# X9-Backplane.net
KiCad netlist of a schematic drawn in EAGLE
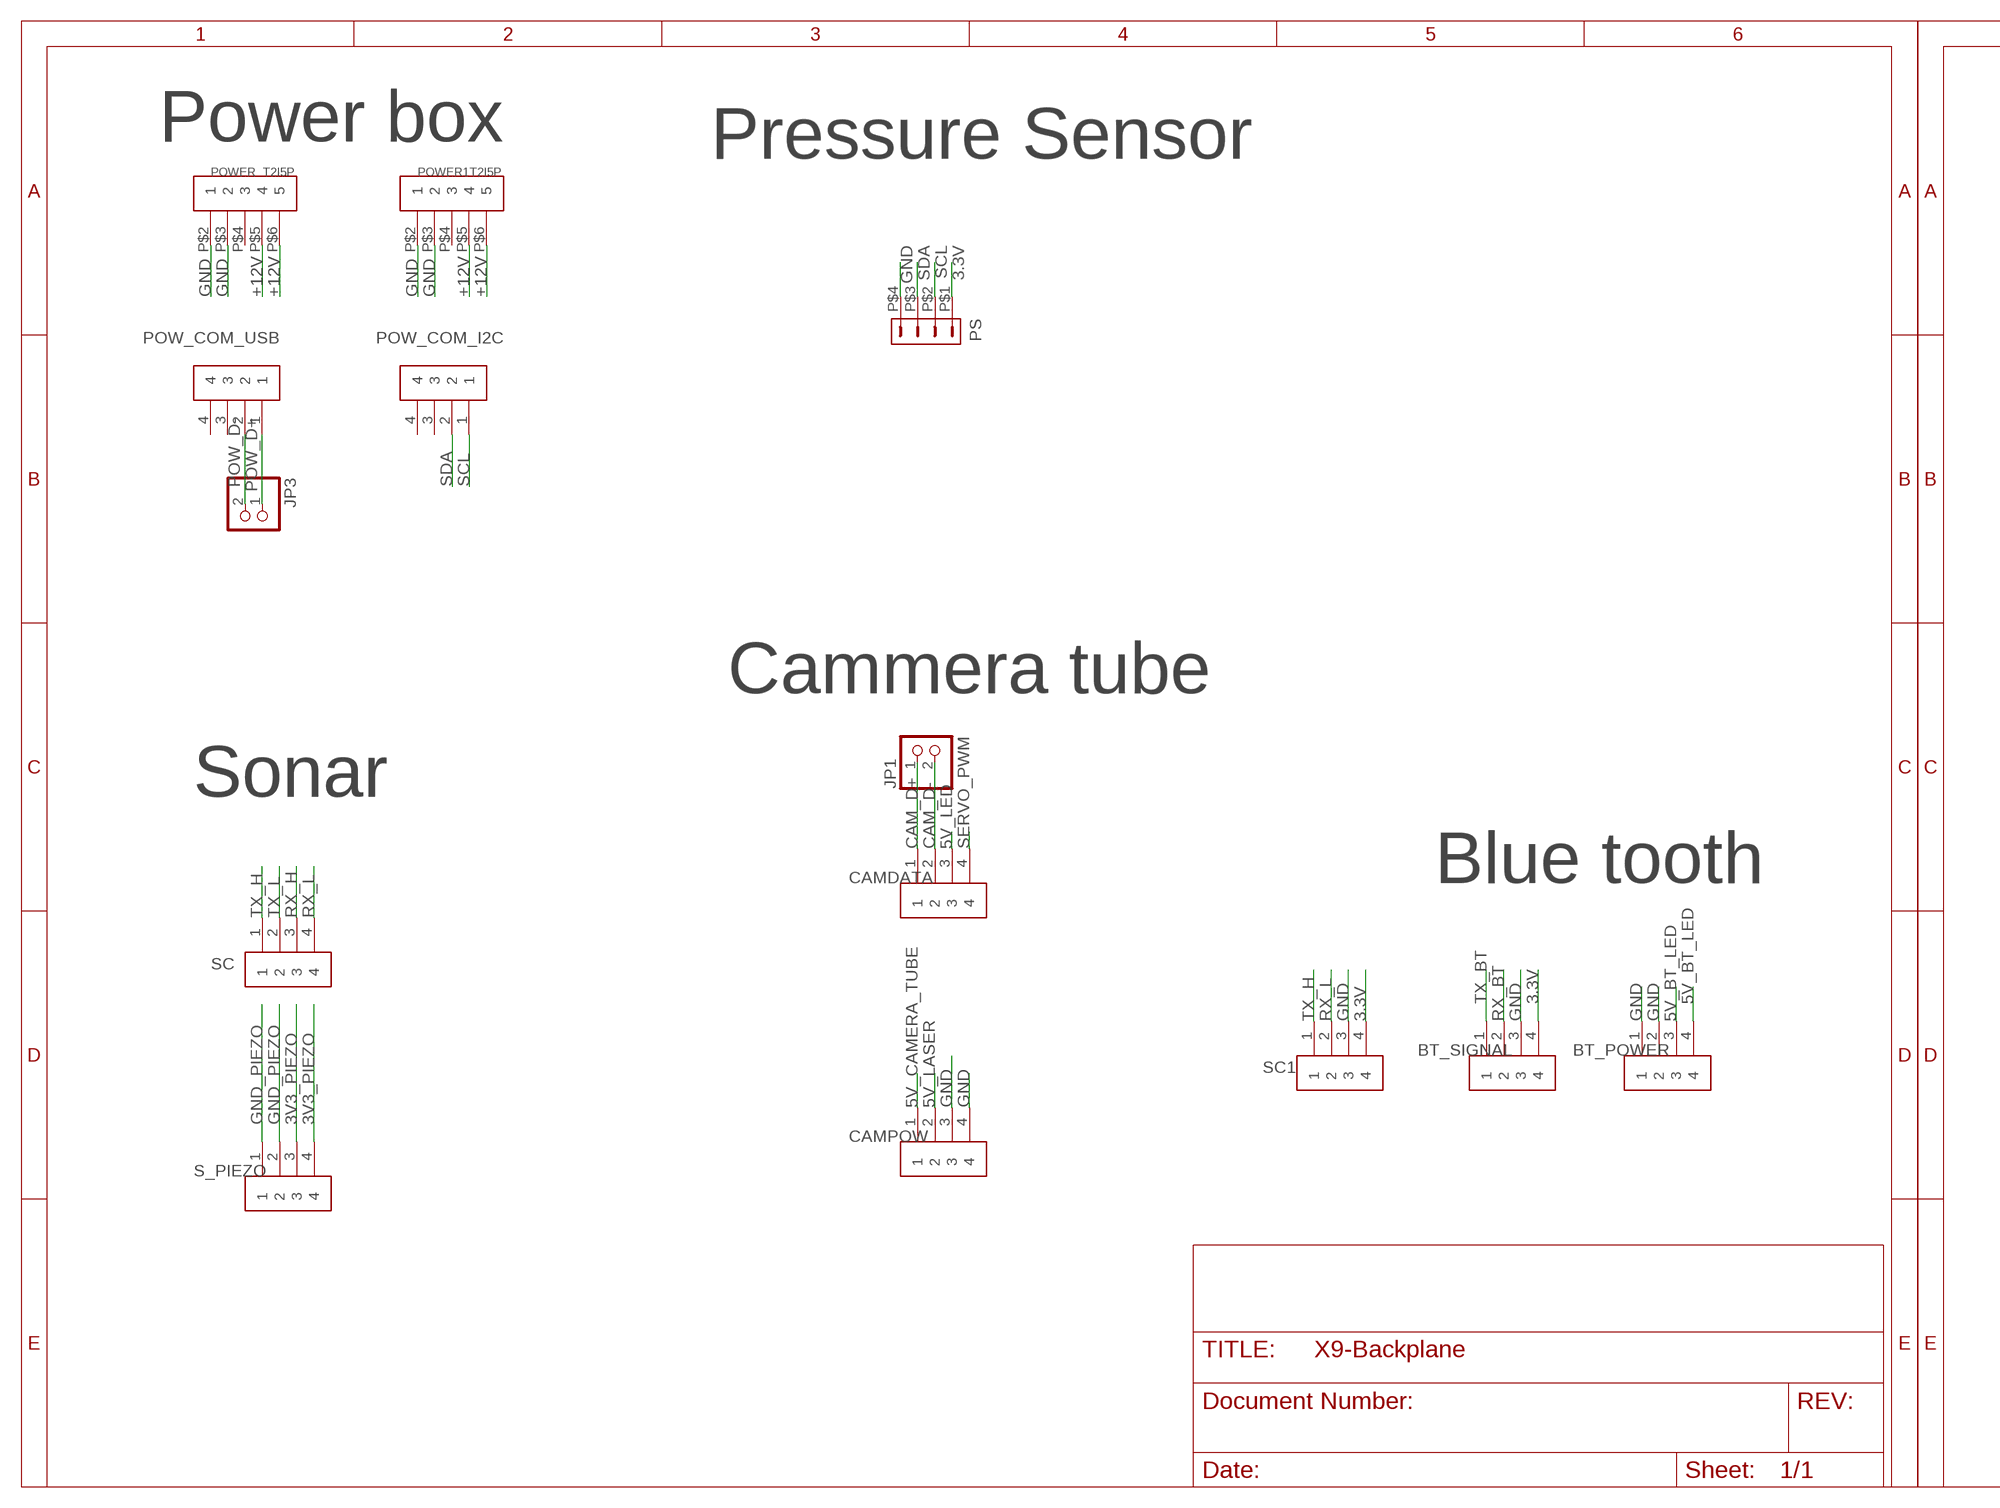
[diagram p0: schematic, sheet 1, part 1 of 2]
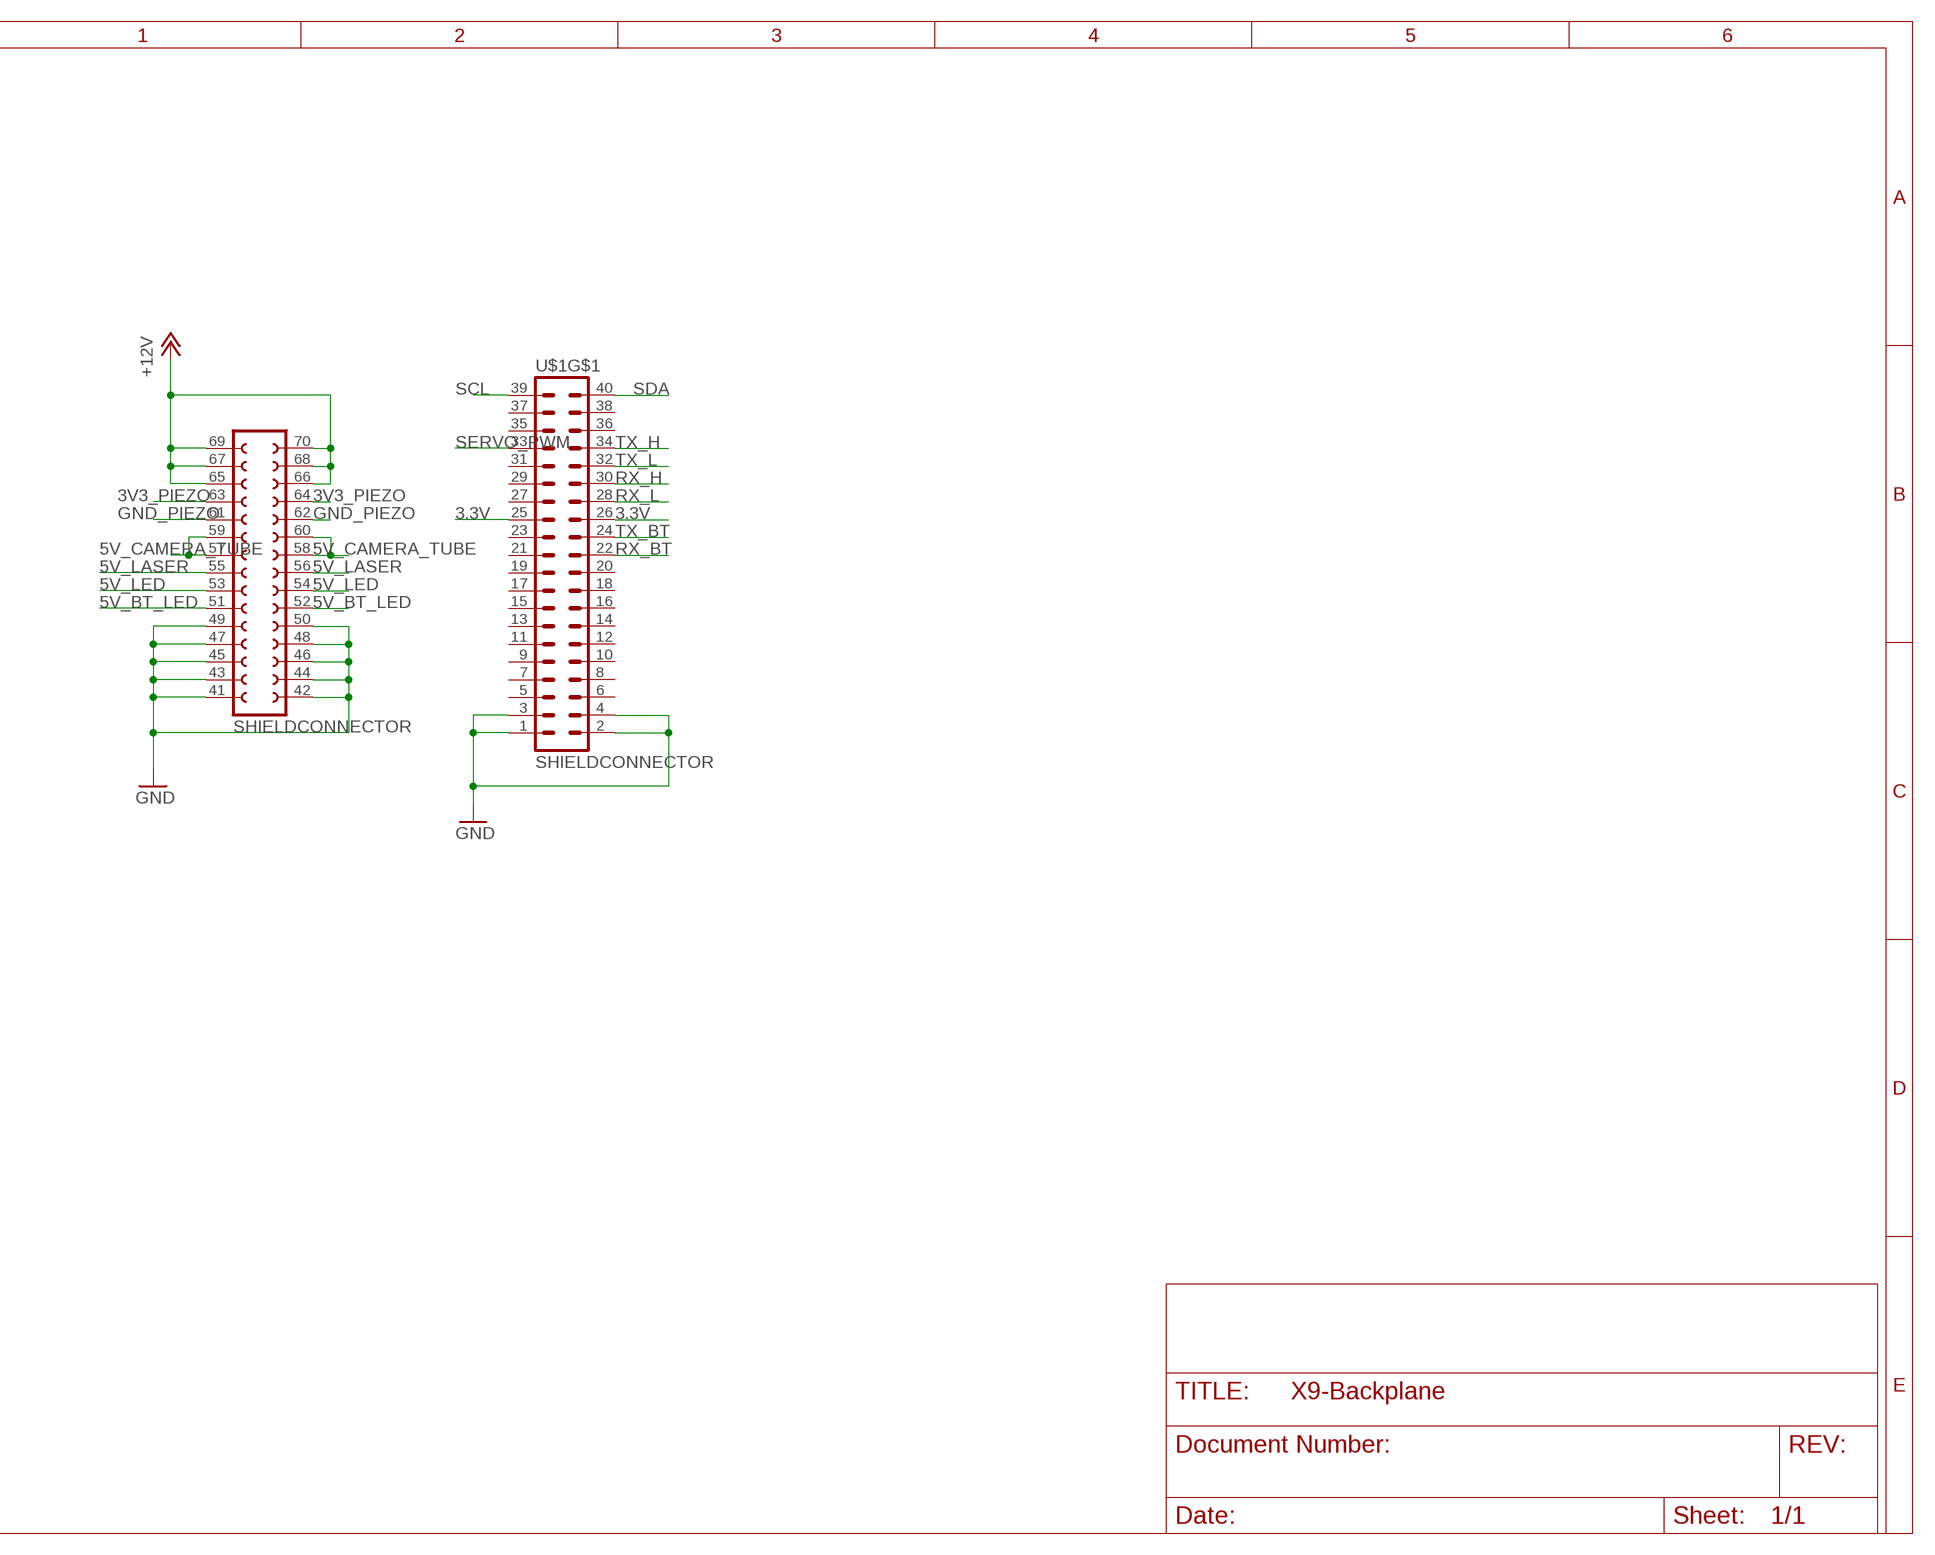
[diagram p1: schematic, sheet 1, part 2 of 2]

(export (version "E")
  (design (tool "Eeschema 10.0.6"))
  (components
    (comp (ref "BT_POWER")
      (value "T2I")
      (footprint "eagle-import:T2I")
      (libsource (lib "eagle-import") (part "T2I"))
    )
    (comp (ref "BT_SIGNAL")
      (value "T2I")
      (footprint "eagle-import:T2I")
      (libsource (lib "eagle-import") (part "T2I"))
    )
    (comp (ref "CAMDATA")
      (value "T2I")
      (footprint "eagle-import:T2I")
      (libsource (lib "eagle-import") (part "T2I"))
    )
    (comp (ref "CAMPOW")
      (value "T2I")
      (footprint "eagle-import:T2I")
      (libsource (lib "eagle-import") (part "T2I"))
    )
    (comp (ref "JP1")
      (value "PINHD-1X2")
      (footprint "eagle-import:1X02")
      (libsource (lib "eagle-import") (part "PINHD-1X2"))
    )
    (comp (ref "JP3")
      (value "PINHD-1X2")
      (footprint "eagle-import:1X02")
      (libsource (lib "eagle-import") (part "PINHD-1X2"))
    )
    (comp (ref "POWER")
      (value "T2I5P")
      (footprint "eagle-import:T2I5P")
      (libsource (lib "eagle-import") (part "T2I5P"))
    )
    (comp (ref "POWER1")
      (value "T2I5P")
      (footprint "eagle-import:T2I5P")
      (libsource (lib "eagle-import") (part "T2I5P"))
    )
    (comp (ref "POW_COM_I2C")
      (value "T2I")
      (footprint "eagle-import:T2I")
      (libsource (lib "eagle-import") (part "T2I"))
    )
    (comp (ref "POW_COM_USB")
      (value "T2I")
      (footprint "eagle-import:T2I")
      (libsource (lib "eagle-import") (part "T2I"))
    )
    (comp (ref "PS")
      (value "DF13-4P-1.25DSA")
      (footprint "eagle-import:DF13-4P-1.25DSA")
      (libsource (lib "eagle-import") (part "DF13-4P-1.25DSA"))
    )
    (comp (ref "SC")
      (value "T2I")
      (footprint "eagle-import:T2I")
      (libsource (lib "eagle-import") (part "T2I"))
    )
    (comp (ref "SC1")
      (value "T2I")
      (footprint "eagle-import:T2I")
      (libsource (lib "eagle-import") (part "T2I"))
    )
    (comp (ref "S_PIEZO")
      (value "T2I")
      (footprint "eagle-import:T2I")
      (libsource (lib "eagle-import") (part "T2I"))
    )
    (comp (ref "U$1")
      (value "SHIELDCONNECTOR")
      (footprint "eagle-import:20X2PIN")
      (libsource (lib "eagle-import") (part "SHIELDCONNECTOR"))
    )
  )
  (nets
    (net (code "1") (name "+12V") (class "Default")
      (node (ref "POWER") (pin "P$5") (pinfunction "4_P$5") (pintype "bidirectional"))
      (node (ref "POWER") (pin "P$6") (pinfunction "5_P$6") (pintype "bidirectional"))
      (node (ref "POWER1") (pin "P$5") (pinfunction "4_P$5") (pintype "bidirectional"))
      (node (ref "POWER1") (pin "P$6") (pinfunction "5_P$6") (pintype "bidirectional"))
      (node (ref "U$1") (pin "65") (pinfunction "12V_65") (pintype "passive"))
      (node (ref "U$1") (pin "66") (pinfunction "12V_66") (pintype "passive"))
      (node (ref "U$1") (pin "67") (pinfunction "12V_67") (pintype "passive"))
      (node (ref "U$1") (pin "68") (pinfunction "12V_68") (pintype "passive"))
      (node (ref "U$1") (pin "69") (pinfunction "12V_69") (pintype "passive"))
      (node (ref "U$1") (pin "70") (pinfunction "12V_70") (pintype "passive"))
    )
    (net (code "2") (name "/3.3V") (class "Default")
      (node (ref "BT_SIGNAL") (pin "4") (pinfunction "4_4") (pintype "bidirectional"))
      (node (ref "PS") (pin "P$1") (pinfunction "1_P$1") (pintype "passive"))
      (node (ref "SC1") (pin "4") (pinfunction "4_4") (pintype "bidirectional"))
      (node (ref "U$1") (pin "25") (pinfunction "25_25") (pintype "passive"))
      (node (ref "U$1") (pin "26") (pinfunction "26_26") (pintype "passive"))
    )
    (net (code "3") (name "/3V3_PIEZO") (class "Default")
      (node (ref "S_PIEZO") (pin "3") (pinfunction "3_3") (pintype "bidirectional"))
      (node (ref "S_PIEZO") (pin "4") (pinfunction "4_4") (pintype "bidirectional"))
      (node (ref "U$1") (pin "63") (pinfunction "3V3_PIEZO_63") (pintype "passive"))
      (node (ref "U$1") (pin "64") (pinfunction "3V3_PIEZO_64") (pintype "passive"))
    )
    (net (code "4") (name "/5V_BT_LED") (class "Default")
      (node (ref "BT_POWER") (pin "3") (pinfunction "3_3") (pintype "bidirectional"))
      (node (ref "BT_POWER") (pin "4") (pinfunction "4_4") (pintype "bidirectional"))
      (node (ref "U$1") (pin "51") (pinfunction "5V_BT_LED_51") (pintype "passive"))
      (node (ref "U$1") (pin "52") (pinfunction "5V_BT_LED_52") (pintype "passive"))
    )
    (net (code "5") (name "/5V_CAMERA_TUBE") (class "Default")
      (node (ref "CAMPOW") (pin "1") (pinfunction "1_1") (pintype "bidirectional"))
      (node (ref "U$1") (pin "57") (pinfunction "5V_CAMERA_TUBE_57") (pintype "passive"))
      (node (ref "U$1") (pin "58") (pinfunction "5V_CAMERA_TUBE_58") (pintype "passive"))
      (node (ref "U$1") (pin "59") (pinfunction "19_59") (pintype "passive"))
      (node (ref "U$1") (pin "60") (pinfunction "20_60") (pintype "passive"))
    )
    (net (code "6") (name "/5V_LASER") (class "Default")
      (node (ref "CAMPOW") (pin "2") (pinfunction "2_2") (pintype "bidirectional"))
      (node (ref "U$1") (pin "55") (pinfunction "5V_LASER_55") (pintype "passive"))
      (node (ref "U$1") (pin "56") (pinfunction "5V_LASER_56") (pintype "passive"))
    )
    (net (code "7") (name "/5V_LED") (class "Default")
      (node (ref "CAMDATA") (pin "3") (pinfunction "3_3") (pintype "bidirectional"))
      (node (ref "U$1") (pin "53") (pinfunction "5V_LED_53") (pintype "passive"))
      (node (ref "U$1") (pin "54") (pinfunction "5V_LED_54") (pintype "passive"))
    )
    (net (code "8") (name "/CAM_D+") (class "Default")
      (node (ref "CAMDATA") (pin "1") (pinfunction "1_1") (pintype "bidirectional"))
      (node (ref "JP1") (pin "1") (pinfunction "1_1") (pintype "passive"))
    )
    (net (code "9") (name "/CAM_D-") (class "Default")
      (node (ref "CAMDATA") (pin "2") (pinfunction "2_2") (pintype "bidirectional"))
      (node (ref "JP1") (pin "2") (pinfunction "2_2") (pintype "passive"))
    )
    (net (code "10") (name "/GND_PIEZO") (class "Default")
      (node (ref "S_PIEZO") (pin "1") (pinfunction "1_1") (pintype "bidirectional"))
      (node (ref "S_PIEZO") (pin "2") (pinfunction "2_2") (pintype "bidirectional"))
      (node (ref "U$1") (pin "61") (pinfunction "GND_PIEZO_61") (pintype "passive"))
      (node (ref "U$1") (pin "62") (pinfunction "GND_PIEZO_62") (pintype "passive"))
    )
    (net (code "11") (name "/POW_D+") (class "Default")
      (node (ref "JP3") (pin "1") (pinfunction "1_1") (pintype "passive"))
      (node (ref "POW_COM_USB") (pin "1") (pinfunction "1_1") (pintype "bidirectional"))
    )
    (net (code "12") (name "/POW_D-") (class "Default")
      (node (ref "JP3") (pin "2") (pinfunction "2_2") (pintype "passive"))
      (node (ref "POW_COM_USB") (pin "2") (pinfunction "2_2") (pintype "bidirectional"))
    )
    (net (code "13") (name "/RX_BT") (class "Default")
      (node (ref "BT_SIGNAL") (pin "2") (pinfunction "2_2") (pintype "bidirectional"))
      (node (ref "U$1") (pin "22") (pinfunction "22_22") (pintype "passive"))
    )
    (net (code "14") (name "/RX_H") (class "Default")
      (node (ref "SC") (pin "3") (pinfunction "3_3") (pintype "bidirectional"))
      (node (ref "U$1") (pin "30") (pinfunction "Z_30") (pintype "passive"))
    )
    (net (code "15") (name "/RX_L") (class "Default")
      (node (ref "SC") (pin "4") (pinfunction "4_4") (pintype "bidirectional"))
      (node (ref "SC1") (pin "2") (pinfunction "2_2") (pintype "bidirectional"))
      (node (ref "U$1") (pin "28") (pinfunction "Y_28") (pintype "passive"))
    )
    (net (code "16") (name "/SCL") (class "Default")
      (node (ref "POW_COM_I2C") (pin "1") (pinfunction "1_1") (pintype "bidirectional"))
      (node (ref "PS") (pin "P$2") (pinfunction "2_P$2") (pintype "passive"))
      (node (ref "U$1") (pin "39") (pinfunction "SCL_39") (pintype "passive"))
    )
    (net (code "17") (name "/SDA") (class "Default")
      (node (ref "POW_COM_I2C") (pin "2") (pinfunction "2_2") (pintype "bidirectional"))
      (node (ref "PS") (pin "P$3") (pinfunction "3_P$3") (pintype "passive"))
      (node (ref "U$1") (pin "40") (pinfunction "SDA_40") (pintype "passive"))
    )
    (net (code "18") (name "/SERVO_PWM") (class "Default")
      (node (ref "CAMDATA") (pin "4") (pinfunction "4_4") (pintype "bidirectional"))
      (node (ref "U$1") (pin "33") (pinfunction "SERVO_PWM_33") (pintype "passive"))
    )
    (net (code "19") (name "/TX_BT") (class "Default")
      (node (ref "BT_SIGNAL") (pin "1") (pinfunction "1_1") (pintype "bidirectional"))
      (node (ref "U$1") (pin "24") (pinfunction "24_24") (pintype "passive"))
    )
    (net (code "20") (name "/TX_H") (class "Default")
      (node (ref "SC") (pin "1") (pinfunction "1_1") (pintype "bidirectional"))
      (node (ref "SC1") (pin "1") (pinfunction "1_1") (pintype "bidirectional"))
      (node (ref "U$1") (pin "34") (pinfunction "A_34") (pintype "passive"))
    )
    (net (code "21") (name "/TX_L") (class "Default")
      (node (ref "SC") (pin "2") (pinfunction "2_2") (pintype "bidirectional"))
      (node (ref "U$1") (pin "32") (pinfunction "B_32") (pintype "passive"))
    )
    (net (code "22") (name "GND") (class "Default")
      (node (ref "BT_POWER") (pin "1") (pinfunction "1_1") (pintype "bidirectional"))
      (node (ref "BT_POWER") (pin "2") (pinfunction "2_2") (pintype "bidirectional"))
      (node (ref "BT_SIGNAL") (pin "3") (pinfunction "3_3") (pintype "bidirectional"))
      (node (ref "CAMPOW") (pin "3") (pinfunction "3_3") (pintype "bidirectional"))
      (node (ref "CAMPOW") (pin "4") (pinfunction "4_4") (pintype "bidirectional"))
      (node (ref "POWER") (pin "P$2") (pinfunction "1_P$2") (pintype "bidirectional"))
      (node (ref "POWER") (pin "P$3") (pinfunction "2_P$3") (pintype "bidirectional"))
      (node (ref "POWER1") (pin "P$2") (pinfunction "1_P$2") (pintype "bidirectional"))
      (node (ref "POWER1") (pin "P$3") (pinfunction "2_P$3") (pintype "bidirectional"))
      (node (ref "PS") (pin "P$4") (pinfunction "4_P$4") (pintype "passive"))
      (node (ref "SC1") (pin "3") (pinfunction "3_3") (pintype "bidirectional"))
      (node (ref "U$1") (pin "1") (pinfunction "1_1") (pintype "passive"))
      (node (ref "U$1") (pin "2") (pinfunction "2_2") (pintype "passive"))
      (node (ref "U$1") (pin "3") (pinfunction "3_3") (pintype "passive"))
      (node (ref "U$1") (pin "4") (pinfunction "4_4") (pintype "passive"))
      (node (ref "U$1") (pin "41") (pinfunction "GND_41") (pintype "passive"))
      (node (ref "U$1") (pin "42") (pinfunction "GND_42") (pintype "passive"))
      (node (ref "U$1") (pin "43") (pinfunction "GND_43") (pintype "passive"))
      (node (ref "U$1") (pin "44") (pinfunction "GND_44") (pintype "passive"))
      (node (ref "U$1") (pin "45") (pinfunction "GND_45") (pintype "passive"))
      (node (ref "U$1") (pin "46") (pinfunction "GND_46") (pintype "passive"))
      (node (ref "U$1") (pin "47") (pinfunction "GND_47") (pintype "passive"))
      (node (ref "U$1") (pin "48") (pinfunction "GND_48") (pintype "passive"))
      (node (ref "U$1") (pin "49") (pinfunction "GND_49") (pintype "passive"))
      (node (ref "U$1") (pin "50") (pinfunction "GND_50") (pintype "passive"))
    )
    (net (code "23") (name "unconnected-(POWER-3-PadP$4)") (class "Default")
      (node (ref "POWER") (pin "P$4") (pinfunction "3_P$4") (pintype "bidirectional"))
    )
    (net (code "24") (name "unconnected-(POWER1-3-PadP$4)") (class "Default")
      (node (ref "POWER1") (pin "P$4") (pinfunction "3_P$4") (pintype "bidirectional"))
    )
    (net (code "25") (name "unconnected-(POW_COM_I2C-Pad3)") (class "Default")
      (node (ref "POW_COM_I2C") (pin "3") (pinfunction "3_3") (pintype "bidirectional"))
    )
    (net (code "26") (name "unconnected-(POW_COM_I2C-Pad4)") (class "Default")
      (node (ref "POW_COM_I2C") (pin "4") (pinfunction "4_4") (pintype "bidirectional"))
    )
    (net (code "27") (name "unconnected-(POW_COM_USB-Pad3)") (class "Default")
      (node (ref "POW_COM_USB") (pin "3") (pinfunction "3_3") (pintype "bidirectional"))
    )
    (net (code "28") (name "unconnected-(POW_COM_USB-Pad4)") (class "Default")
      (node (ref "POW_COM_USB") (pin "4") (pinfunction "4_4") (pintype "bidirectional"))
    )
    (net (code "29") (name "unconnected-(U$1-Pad5)") (class "Default")
      (node (ref "U$1") (pin "5") (pinfunction "5_5") (pintype "passive"))
    )
    (net (code "30") (name "unconnected-(U$1-Pad6)") (class "Default")
      (node (ref "U$1") (pin "6") (pinfunction "6_6") (pintype "passive"))
    )
    (net (code "31") (name "unconnected-(U$1-Pad7)") (class "Default")
      (node (ref "U$1") (pin "7") (pinfunction "7_7") (pintype "passive"))
    )
    (net (code "32") (name "unconnected-(U$1-Pad8)") (class "Default")
      (node (ref "U$1") (pin "8") (pinfunction "8_8") (pintype "passive"))
    )
    (net (code "33") (name "unconnected-(U$1-Pad9)") (class "Default")
      (node (ref "U$1") (pin "9") (pinfunction "9_9") (pintype "passive"))
    )
    (net (code "34") (name "unconnected-(U$1-Pad10)") (class "Default")
      (node (ref "U$1") (pin "10") (pinfunction "10_10") (pintype "passive"))
    )
    (net (code "35") (name "unconnected-(U$1-Pad11)") (class "Default")
      (node (ref "U$1") (pin "11") (pinfunction "11_11") (pintype "passive"))
    )
    (net (code "36") (name "unconnected-(U$1-Pad12)") (class "Default")
      (node (ref "U$1") (pin "12") (pinfunction "12_12") (pintype "passive"))
    )
    (net (code "37") (name "unconnected-(U$1-Pad13)") (class "Default")
      (node (ref "U$1") (pin "13") (pinfunction "13_13") (pintype "passive"))
    )
    (net (code "38") (name "unconnected-(U$1-Pad14)") (class "Default")
      (node (ref "U$1") (pin "14") (pinfunction "14_14") (pintype "passive"))
    )
    (net (code "39") (name "unconnected-(U$1-Pad15)") (class "Default")
      (node (ref "U$1") (pin "15") (pinfunction "15_15") (pintype "passive"))
    )
    (net (code "40") (name "unconnected-(U$1-Pad16)") (class "Default")
      (node (ref "U$1") (pin "16") (pinfunction "16_16") (pintype "passive"))
    )
    (net (code "41") (name "unconnected-(U$1-Pad17)") (class "Default")
      (node (ref "U$1") (pin "17") (pinfunction "17_17") (pintype "passive"))
    )
    (net (code "42") (name "unconnected-(U$1-Pad18)") (class "Default")
      (node (ref "U$1") (pin "18") (pinfunction "18_18") (pintype "passive"))
    )
    (net (code "43") (name "unconnected-(U$1-Pad19)") (class "Default")
      (node (ref "U$1") (pin "19") (pinfunction "19_19") (pintype "passive"))
    )
    (net (code "44") (name "unconnected-(U$1-Pad20)") (class "Default")
      (node (ref "U$1") (pin "20") (pinfunction "20_20") (pintype "passive"))
    )
    (net (code "45") (name "unconnected-(U$1-Pad21)") (class "Default")
      (node (ref "U$1") (pin "21") (pinfunction "21_21") (pintype "passive"))
    )
    (net (code "46") (name "unconnected-(U$1-Pad23)") (class "Default")
      (node (ref "U$1") (pin "23") (pinfunction "23_23") (pintype "passive"))
    )
    (net (code "47") (name "unconnected-(U$1-Pad27)") (class "Default")
      (node (ref "U$1") (pin "27") (pinfunction "27_27") (pintype "passive"))
    )
    (net (code "48") (name "unconnected-(U$1-Pad29)") (class "Default")
      (node (ref "U$1") (pin "29") (pinfunction "29_29") (pintype "passive"))
    )
    (net (code "49") (name "unconnected-(U$1-Pad31)") (class "Default")
      (node (ref "U$1") (pin "31") (pinfunction "31_31") (pintype "passive"))
    )
    (net (code "50") (name "unconnected-(U$1A-DSCLM-Pad36)") (class "Default")
      (node (ref "U$1") (pin "36") (pinfunction "DSCLM_36") (pintype "passive"))
    )
    (net (code "51") (name "unconnected-(U$1A-DSCLP-Pad35)") (class "Default")
      (node (ref "U$1") (pin "35") (pinfunction "DSCLP_35") (pintype "passive"))
    )
    (net (code "52") (name "unconnected-(U$1A-DSDAM-Pad38)") (class "Default")
      (node (ref "U$1") (pin "38") (pinfunction "DSDAM_38") (pintype "passive"))
    )
    (net (code "53") (name "unconnected-(U$1A-DSDAP-Pad37)") (class "Default")
      (node (ref "U$1") (pin "37") (pinfunction "DSDAP_37") (pintype "passive"))
    )
  )
)
